# XMini.net
KiCad netlist of a schematic drawn in Altium Designer
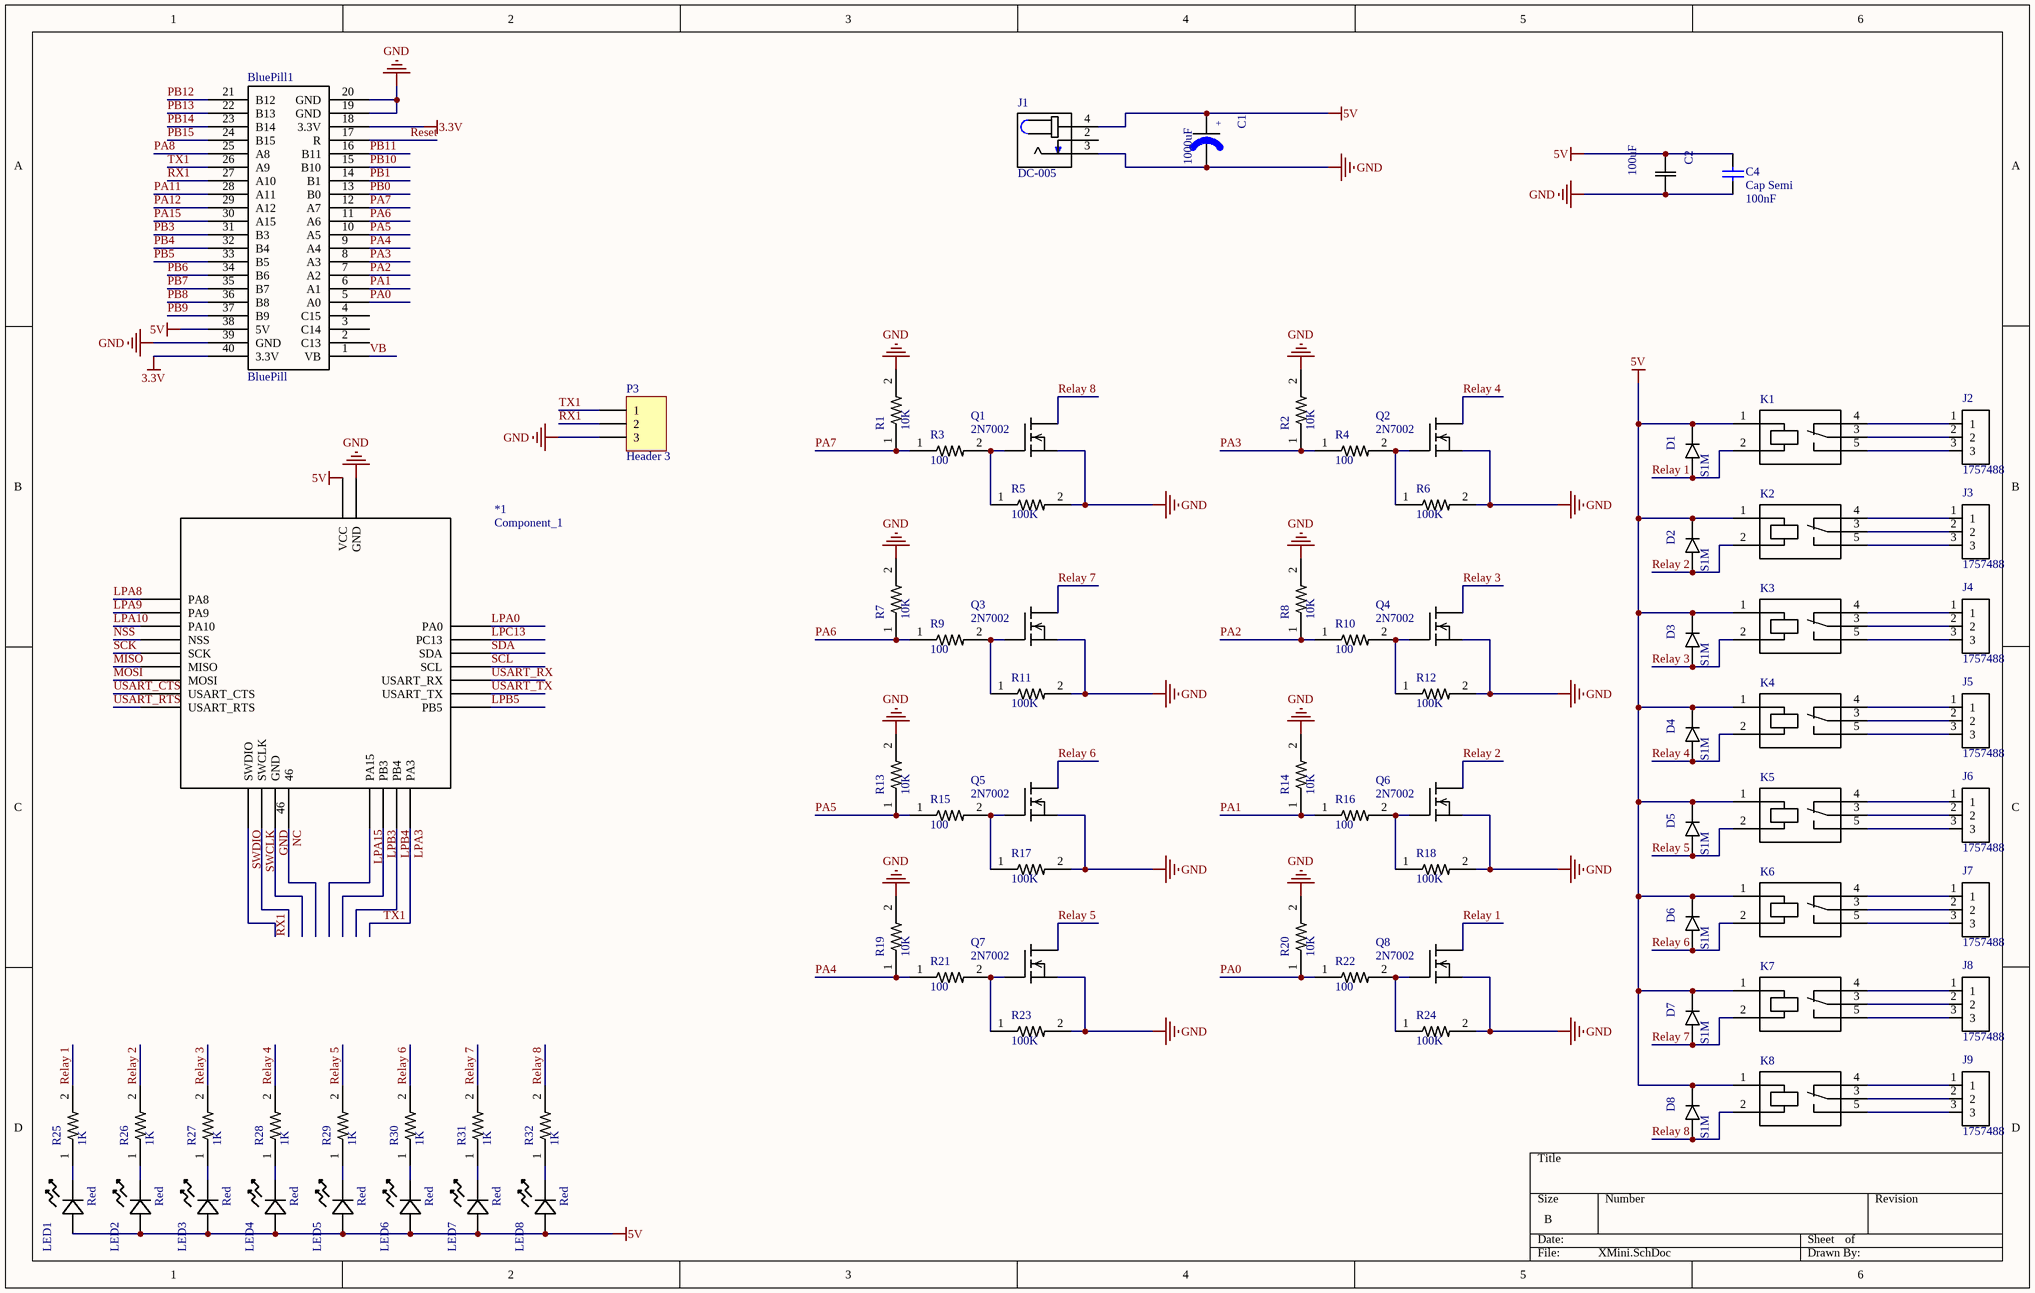
[diagram p0: XMini.SchDoc]

(export (version "E")
  (design (tool "Eeschema 10.0.6"))
  (components
    (comp (ref "*1")
      (value "Component_1")
      (footprint "Lora_Board")
      (libsource (lib "Lora Board") (part "Component_1"))
    )
    (comp (ref "BluePill1")
      (value "BluePill")
      (footprint "stm32 Blue pill")
      (description "Blue Pill Module")
      (libsource (lib "Schlib1") (part "Stm32BluePill"))
    )
    (comp (ref "C1")
      (value "1000uF")
      (footprint "*CAPAE1030X1050N")
      (fields (field (name "MF") "Cornell Dubilier") (field (name "MP") "HZA107M050G24T-F"))
      (libsource (lib "HZA107M050G24T-F") (part "HZA107M050G24T-F"))
    )
    (comp (ref "C2")
      (value "100uF")
      (footprint "*CAPCP7343X430N")
      (description "Capacitor tantalum TAJ 2717 330uF 6.3V")
      (fields (field (name "MF") "AVX") (field (name "MP") "TAJE337K006R"))
      (libsource (lib "TAJE337K006R") (part "TAJE337K006R"))
    )
    (comp (ref "C4")
      (value "Cap Semi")
      (footprint "C1206")
      (description "Capacitor (Semiconductor SIM Model)")
      (fields (field (name "ALTIUM_VALUE") "100nF") (field (name "PUBLISHER") "Altium Limited"))
      (libsource (lib "Miscellaneous Devices") (part "Cap Semi"))
    )
    (comp (ref "D1")
      (value "S1M")
      (footprint "SMD Diode*DIOM5227X270NSMD DiodeS1MSMD DiodePrimarySMD Diode")
      (description "S1 Series 1000 V 1 A 1 uA Surface Mount General Purpose Rectifier - DO-214AC")
      (fields (field (name "MF") "ON Semiconductor"))
      (libsource (lib "S1M") (part "S1M"))
    )
    (comp (ref "D2")
      (value "S1M")
      (footprint "SMD Diode*DIOM5227X270NSMD DiodeS1MSMD DiodePrimarySMD Diode")
      (description "S1 Series 1000 V 1 A 1 uA Surface Mount General Purpose Rectifier - DO-214AC")
      (fields (field (name "MF") "ON Semiconductor"))
      (libsource (lib "S1M") (part "S1M"))
    )
    (comp (ref "D3")
      (value "S1M")
      (footprint "SMD Diode*DIOM5227X270NSMD DiodeS1MSMD DiodePrimarySMD Diode")
      (description "S1 Series 1000 V 1 A 1 uA Surface Mount General Purpose Rectifier - DO-214AC")
      (fields (field (name "MF") "ON Semiconductor"))
      (libsource (lib "S1M") (part "S1M"))
    )
    (comp (ref "D4")
      (value "S1M")
      (footprint "SMD Diode*DIOM5227X270NSMD DiodeS1MSMD DiodePrimarySMD Diode")
      (description "S1 Series 1000 V 1 A 1 uA Surface Mount General Purpose Rectifier - DO-214AC")
      (fields (field (name "MF") "ON Semiconductor"))
      (libsource (lib "S1M") (part "S1M"))
    )
    (comp (ref "D5")
      (value "S1M")
      (footprint "SMD Diode*DIOM5227X270NSMD DiodeS1MSMD DiodePrimarySMD Diode")
      (description "S1 Series 1000 V 1 A 1 uA Surface Mount General Purpose Rectifier - DO-214AC")
      (fields (field (name "MF") "ON Semiconductor"))
      (libsource (lib "S1M") (part "S1M"))
    )
    (comp (ref "D6")
      (value "S1M")
      (footprint "SMD Diode*DIOM5227X270NSMD DiodeS1MSMD DiodePrimarySMD Diode")
      (description "S1 Series 1000 V 1 A 1 uA Surface Mount General Purpose Rectifier - DO-214AC")
      (fields (field (name "MF") "ON Semiconductor"))
      (libsource (lib "S1M") (part "S1M"))
    )
    (comp (ref "D7")
      (value "S1M")
      (footprint "SMD Diode*DIOM5227X270NSMD DiodeS1MSMD DiodePrimarySMD Diode")
      (description "S1 Series 1000 V 1 A 1 uA Surface Mount General Purpose Rectifier - DO-214AC")
      (fields (field (name "MF") "ON Semiconductor"))
      (libsource (lib "S1M") (part "S1M"))
    )
    (comp (ref "D8")
      (value "S1M")
      (footprint "SMD Diode*DIOM5227X270NSMD DiodeS1MSMD DiodePrimarySMD Diode")
      (description "S1 Series 1000 V 1 A 1 uA Surface Mount General Purpose Rectifier - DO-214AC")
      (fields (field (name "MF") "ON Semiconductor"))
      (libsource (lib "S1M") (part "S1M"))
    )
    (comp (ref "J1")
      (value "DC-005")
      (footprint "*NINIGI_DC-005")
      (fields (field (name "MF") "Littelfuse Inc."))
      (libsource (lib "DC-005") (part "DC-005"))
    )
    (comp (ref "J2")
      (value "1757488")
      (footprint "*PHOENIX_1757488")
      (description "Conn; TermBlk; PCB; Header; SnglLvl; 90DegAngl; Sldr; 3Pole; 5mmPitch; COMBICON")
      (fields (field (name "MF") "Phoenix Contact"))
      (libsource (lib "1757488") (part "1757488"))
    )
    (comp (ref "J3")
      (value "1757488")
      (footprint "*PHOENIX_1757488")
      (description "Conn; TermBlk; PCB; Header; SnglLvl; 90DegAngl; Sldr; 3Pole; 5mmPitch; COMBICON")
      (fields (field (name "MF") "Phoenix Contact"))
      (libsource (lib "1757488") (part "1757488"))
    )
    (comp (ref "J4")
      (value "1757488")
      (footprint "*PHOENIX_1757488")
      (description "Conn; TermBlk; PCB; Header; SnglLvl; 90DegAngl; Sldr; 3Pole; 5mmPitch; COMBICON")
      (fields (field (name "MF") "Phoenix Contact"))
      (libsource (lib "1757488") (part "1757488"))
    )
    (comp (ref "J5")
      (value "1757488")
      (footprint "*PHOENIX_1757488")
      (description "Conn; TermBlk; PCB; Header; SnglLvl; 90DegAngl; Sldr; 3Pole; 5mmPitch; COMBICON")
      (fields (field (name "MF") "Phoenix Contact"))
      (libsource (lib "1757488") (part "1757488"))
    )
    (comp (ref "J6")
      (value "1757488")
      (footprint "*PHOENIX_1757488")
      (description "Conn; TermBlk; PCB; Header; SnglLvl; 90DegAngl; Sldr; 3Pole; 5mmPitch; COMBICON")
      (fields (field (name "MF") "Phoenix Contact"))
      (libsource (lib "1757488") (part "1757488"))
    )
    (comp (ref "J7")
      (value "1757488")
      (footprint "*PHOENIX_1757488")
      (description "Conn; TermBlk; PCB; Header; SnglLvl; 90DegAngl; Sldr; 3Pole; 5mmPitch; COMBICON")
      (fields (field (name "MF") "Phoenix Contact"))
      (libsource (lib "1757488") (part "1757488"))
    )
    (comp (ref "J8")
      (value "1757488")
      (footprint "*PHOENIX_1757488")
      (description "Conn; TermBlk; PCB; Header; SnglLvl; 90DegAngl; Sldr; 3Pole; 5mmPitch; COMBICON")
      (fields (field (name "MF") "Phoenix Contact"))
      (libsource (lib "1757488") (part "1757488"))
    )
    (comp (ref "J9")
      (value "1757488")
      (footprint "*PHOENIX_1757488")
      (description "Conn; TermBlk; PCB; Header; SnglLvl; 90DegAngl; Sldr; 3Pole; 5mmPitch; COMBICON")
      (fields (field (name "MF") "Phoenix Contact"))
      (libsource (lib "1757488") (part "1757488"))
    )
    (comp (ref "K1")
      (value "1-1721150-0")
      (footprint "*TE_ORWH-SH-105D1F,000")
      (description "General Purpose Relay, ORWH Series, Power, Non Latching, SPDT, 5 VDC, 10 A")
      (fields (field (name "MF") "TE Connectivity") (field (name "MP") "ORWH-SH-105D1F,000"))
      (libsource (lib "ORWH-SH-105D1F_000") (part "ORWH-SH-105D1F,000"))
    )
    (comp (ref "K2")
      (value "1-1721150-0")
      (footprint "*TE_ORWH-SH-105D1F,000")
      (description "General Purpose Relay, ORWH Series, Power, Non Latching, SPDT, 5 VDC, 10 A")
      (fields (field (name "MF") "TE Connectivity") (field (name "MP") "ORWH-SH-105D1F,000"))
      (libsource (lib "ORWH-SH-105D1F_000") (part "ORWH-SH-105D1F,000"))
    )
    (comp (ref "K3")
      (value "1-1721150-0")
      (footprint "*TE_ORWH-SH-105D1F,000")
      (description "General Purpose Relay, ORWH Series, Power, Non Latching, SPDT, 5 VDC, 10 A")
      (fields (field (name "MF") "TE Connectivity") (field (name "MP") "ORWH-SH-105D1F,000"))
      (libsource (lib "ORWH-SH-105D1F_000") (part "ORWH-SH-105D1F,000"))
    )
    (comp (ref "K4")
      (value "1-1721150-0")
      (footprint "*TE_ORWH-SH-105D1F,000")
      (description "General Purpose Relay, ORWH Series, Power, Non Latching, SPDT, 5 VDC, 10 A")
      (fields (field (name "MF") "TE Connectivity") (field (name "MP") "ORWH-SH-105D1F,000"))
      (libsource (lib "ORWH-SH-105D1F_000") (part "ORWH-SH-105D1F,000"))
    )
    (comp (ref "K5")
      (value "1-1721150-0")
      (footprint "*TE_ORWH-SH-105D1F,000")
      (description "General Purpose Relay, ORWH Series, Power, Non Latching, SPDT, 5 VDC, 10 A")
      (fields (field (name "MF") "TE Connectivity") (field (name "MP") "ORWH-SH-105D1F,000"))
      (libsource (lib "ORWH-SH-105D1F_000") (part "ORWH-SH-105D1F,000"))
    )
    (comp (ref "K6")
      (value "1-1721150-0")
      (footprint "*TE_ORWH-SH-105D1F,000")
      (description "General Purpose Relay, ORWH Series, Power, Non Latching, SPDT, 5 VDC, 10 A")
      (fields (field (name "MF") "TE Connectivity") (field (name "MP") "ORWH-SH-105D1F,000"))
      (libsource (lib "ORWH-SH-105D1F_000") (part "ORWH-SH-105D1F,000"))
    )
    (comp (ref "K7")
      (value "1-1721150-0")
      (footprint "*TE_ORWH-SH-105D1F,000")
      (description "General Purpose Relay, ORWH Series, Power, Non Latching, SPDT, 5 VDC, 10 A")
      (fields (field (name "MF") "TE Connectivity") (field (name "MP") "ORWH-SH-105D1F,000"))
      (libsource (lib "ORWH-SH-105D1F_000") (part "ORWH-SH-105D1F,000"))
    )
    (comp (ref "K8")
      (value "1-1721150-0")
      (footprint "*TE_ORWH-SH-105D1F,000")
      (description "General Purpose Relay, ORWH Series, Power, Non Latching, SPDT, 5 VDC, 10 A")
      (fields (field (name "MF") "TE Connectivity") (field (name "MP") "ORWH-SH-105D1F,000"))
      (libsource (lib "ORWH-SH-105D1F_000") (part "ORWH-SH-105D1F,000"))
    )
    (comp (ref "LED1")
      (value "Red")
      (footprint "*LED_597-3111-407F")
      (description "LED RED CLEAR 1206 SMD")
      (fields (field (name "MF") "Dialight") (field (name "MP") "5973111407F"))
      (libsource (lib "597-3111-407F") (part "597-3111-407F"))
    )
    (comp (ref "LED2")
      (value "Red")
      (footprint "*LED_597-3111-407F")
      (description "LED RED CLEAR 1206 SMD")
      (fields (field (name "MF") "Dialight") (field (name "MP") "5973111407F"))
      (libsource (lib "597-3111-407F") (part "597-3111-407F"))
    )
    (comp (ref "LED3")
      (value "Red")
      (footprint "*LED_597-3111-407F")
      (description "LED RED CLEAR 1206 SMD")
      (fields (field (name "MF") "Dialight") (field (name "MP") "5973111407F"))
      (libsource (lib "597-3111-407F") (part "597-3111-407F"))
    )
    (comp (ref "LED4")
      (value "Red")
      (footprint "*LED_597-3111-407F")
      (description "LED RED CLEAR 1206 SMD")
      (fields (field (name "MF") "Dialight") (field (name "MP") "5973111407F"))
      (libsource (lib "597-3111-407F") (part "597-3111-407F"))
    )
    (comp (ref "LED5")
      (value "Red")
      (footprint "*LED_597-3111-407F")
      (description "LED RED CLEAR 1206 SMD")
      (fields (field (name "MF") "Dialight") (field (name "MP") "5973111407F"))
      (libsource (lib "597-3111-407F") (part "597-3111-407F"))
    )
    (comp (ref "LED6")
      (value "Red")
      (footprint "*LED_597-3111-407F")
      (description "LED RED CLEAR 1206 SMD")
      (fields (field (name "MF") "Dialight") (field (name "MP") "5973111407F"))
      (libsource (lib "597-3111-407F") (part "597-3111-407F"))
    )
    (comp (ref "LED7")
      (value "Red")
      (footprint "*LED_597-3111-407F")
      (description "LED RED CLEAR 1206 SMD")
      (fields (field (name "MF") "Dialight") (field (name "MP") "5973111407F"))
      (libsource (lib "597-3111-407F") (part "597-3111-407F"))
    )
    (comp (ref "LED8")
      (value "Red")
      (footprint "*LED_597-3111-407F")
      (description "LED RED CLEAR 1206 SMD")
      (fields (field (name "MF") "Dialight") (field (name "MP") "5973111407F"))
      (libsource (lib "597-3111-407F") (part "597-3111-407F"))
    )
    (comp (ref "P3")
      (value "Header 3")
      (footprint "HDR1X3")
      (description "Header, 3-Pin")
      (fields (field (name "PUBLISHER") "Altium Limited"))
      (libsource (lib "Miscellaneous Connectors") (part "Header 3"))
    )
    (comp (ref "Q1")
      (value "2N7002")
      (footprint "*SOT23")
      (description "Transistor NPN Mos 2N7002 SILICONIX miliampere=100 V=60 SOt23")
      (fields (field (name "MF") "STMicroelectronics"))
      (libsource (lib "2N7002") (part "2N7002"))
    )
    (comp (ref "Q2")
      (value "2N7002")
      (footprint "*SOT23")
      (description "Transistor NPN Mos 2N7002 SILICONIX miliampere=100 V=60 SOt23")
      (fields (field (name "MF") "STMicroelectronics"))
      (libsource (lib "2N7002") (part "2N7002"))
    )
    (comp (ref "Q3")
      (value "2N7002")
      (footprint "*SOT23")
      (description "Transistor NPN Mos 2N7002 SILICONIX miliampere=100 V=60 SOt23")
      (fields (field (name "MF") "STMicroelectronics"))
      (libsource (lib "2N7002") (part "2N7002"))
    )
    (comp (ref "Q4")
      (value "2N7002")
      (footprint "*SOT23")
      (description "Transistor NPN Mos 2N7002 SILICONIX miliampere=100 V=60 SOt23")
      (fields (field (name "MF") "STMicroelectronics"))
      (libsource (lib "2N7002") (part "2N7002"))
    )
    (comp (ref "Q5")
      (value "2N7002")
      (footprint "*SOT23")
      (description "Transistor NPN Mos 2N7002 SILICONIX miliampere=100 V=60 SOt23")
      (fields (field (name "MF") "STMicroelectronics"))
      (libsource (lib "2N7002") (part "2N7002"))
    )
    (comp (ref "Q6")
      (value "2N7002")
      (footprint "*SOT23")
      (description "Transistor NPN Mos 2N7002 SILICONIX miliampere=100 V=60 SOt23")
      (fields (field (name "MF") "STMicroelectronics"))
      (libsource (lib "2N7002") (part "2N7002"))
    )
    (comp (ref "Q7")
      (value "2N7002")
      (footprint "*SOT23")
      (description "Transistor NPN Mos 2N7002 SILICONIX miliampere=100 V=60 SOt23")
      (fields (field (name "MF") "STMicroelectronics"))
      (libsource (lib "2N7002") (part "2N7002"))
    )
    (comp (ref "Q8")
      (value "2N7002")
      (footprint "*SOT23")
      (description "Transistor NPN Mos 2N7002 SILICONIX miliampere=100 V=60 SOt23")
      (fields (field (name "MF") "STMicroelectronics"))
      (libsource (lib "2N7002") (part "2N7002"))
    )
    (comp (ref "R1")
      (value "10K")
      (footprint "*RESC3116X65N")
      (description "Res Smd 120k Ohm 0.5% 1/8w 1206")
      (fields (field (name "MF") "Yageo") (field (name "MP") "RT1206DRE07120KL"))
      (libsource (lib "RT1206DRE07120KL") (part "RT1206DRE07120KL"))
    )
    (comp (ref "R2")
      (value "10K")
      (footprint "*RESC3116X65N")
      (description "Res Smd 120k Ohm 0.5% 1/8w 1206")
      (fields (field (name "MF") "Yageo") (field (name "MP") "RT1206DRE07120KL"))
      (libsource (lib "RT1206DRE07120KL") (part "RT1206DRE07120KL"))
    )
    (comp (ref "R3")
      (value "100")
      (footprint "*RESC3116X65N")
      (description "Res Smd 120k Ohm 0.5% 1/8w 1206")
      (fields (field (name "MF") "Yageo") (field (name "MP") "RT1206DRE07120KL"))
      (libsource (lib "RT1206DRE07120KL") (part "RT1206DRE07120KL"))
    )
    (comp (ref "R4")
      (value "100")
      (footprint "*RESC3116X65N")
      (description "Res Smd 120k Ohm 0.5% 1/8w 1206")
      (fields (field (name "MF") "Yageo") (field (name "MP") "RT1206DRE07120KL"))
      (libsource (lib "RT1206DRE07120KL") (part "RT1206DRE07120KL"))
    )
    (comp (ref "R5")
      (value "100K")
      (footprint "*RESC3116X65N")
      (description "Res Smd 120k Ohm 0.5% 1/8w 1206")
      (fields (field (name "MF") "Yageo") (field (name "MP") "RT1206DRE07120KL"))
      (libsource (lib "RT1206DRE07120KL") (part "RT1206DRE07120KL"))
    )
    (comp (ref "R6")
      (value "100K")
      (footprint "*RESC3116X65N")
      (description "Res Smd 120k Ohm 0.5% 1/8w 1206")
      (fields (field (name "MF") "Yageo") (field (name "MP") "RT1206DRE07120KL"))
      (libsource (lib "RT1206DRE07120KL") (part "RT1206DRE07120KL"))
    )
    (comp (ref "R7")
      (value "10K")
      (footprint "*RESC3116X65N")
      (description "Res Smd 120k Ohm 0.5% 1/8w 1206")
      (fields (field (name "MF") "Yageo") (field (name "MP") "RT1206DRE07120KL"))
      (libsource (lib "RT1206DRE07120KL") (part "RT1206DRE07120KL"))
    )
    (comp (ref "R8")
      (value "10K")
      (footprint "*RESC3116X65N")
      (description "Res Smd 120k Ohm 0.5% 1/8w 1206")
      (fields (field (name "MF") "Yageo") (field (name "MP") "RT1206DRE07120KL"))
      (libsource (lib "RT1206DRE07120KL") (part "RT1206DRE07120KL"))
    )
    (comp (ref "R9")
      (value "100")
      (footprint "*RESC3116X65N")
      (description "Res Smd 120k Ohm 0.5% 1/8w 1206")
      (fields (field (name "MF") "Yageo") (field (name "MP") "RT1206DRE07120KL"))
      (libsource (lib "RT1206DRE07120KL") (part "RT1206DRE07120KL"))
    )
    (comp (ref "R10")
      (value "100")
      (footprint "*RESC3116X65N")
      (description "Res Smd 120k Ohm 0.5% 1/8w 1206")
      (fields (field (name "MF") "Yageo") (field (name "MP") "RT1206DRE07120KL"))
      (libsource (lib "RT1206DRE07120KL") (part "RT1206DRE07120KL"))
    )
    (comp (ref "R11")
      (value "100K")
      (footprint "*RESC3116X65N")
      (description "Res Smd 120k Ohm 0.5% 1/8w 1206")
      (fields (field (name "MF") "Yageo") (field (name "MP") "RT1206DRE07120KL"))
      (libsource (lib "RT1206DRE07120KL") (part "RT1206DRE07120KL"))
    )
    (comp (ref "R12")
      (value "100K")
      (footprint "*RESC3116X65N")
      (description "Res Smd 120k Ohm 0.5% 1/8w 1206")
      (fields (field (name "MF") "Yageo") (field (name "MP") "RT1206DRE07120KL"))
      (libsource (lib "RT1206DRE07120KL") (part "RT1206DRE07120KL"))
    )
    (comp (ref "R13")
      (value "10K")
      (footprint "*RESC3116X65N")
      (description "Res Smd 120k Ohm 0.5% 1/8w 1206")
      (fields (field (name "MF") "Yageo") (field (name "MP") "RT1206DRE07120KL"))
      (libsource (lib "RT1206DRE07120KL") (part "RT1206DRE07120KL"))
    )
    (comp (ref "R14")
      (value "10K")
      (footprint "*RESC3116X65N")
      (description "Res Smd 120k Ohm 0.5% 1/8w 1206")
      (fields (field (name "MF") "Yageo") (field (name "MP") "RT1206DRE07120KL"))
      (libsource (lib "RT1206DRE07120KL") (part "RT1206DRE07120KL"))
    )
    (comp (ref "R15")
      (value "100")
      (footprint "*RESC3116X65N")
      (description "Res Smd 120k Ohm 0.5% 1/8w 1206")
      (fields (field (name "MF") "Yageo") (field (name "MP") "RT1206DRE07120KL"))
      (libsource (lib "RT1206DRE07120KL") (part "RT1206DRE07120KL"))
    )
    (comp (ref "R16")
      (value "100")
      (footprint "*RESC3116X65N")
      (description "Res Smd 120k Ohm 0.5% 1/8w 1206")
      (fields (field (name "MF") "Yageo") (field (name "MP") "RT1206DRE07120KL"))
      (libsource (lib "RT1206DRE07120KL") (part "RT1206DRE07120KL"))
    )
    (comp (ref "R17")
      (value "100K")
      (footprint "*RESC3116X65N")
      (description "Res Smd 120k Ohm 0.5% 1/8w 1206")
      (fields (field (name "MF") "Yageo") (field (name "MP") "RT1206DRE07120KL"))
      (libsource (lib "RT1206DRE07120KL") (part "RT1206DRE07120KL"))
    )
    (comp (ref "R18")
      (value "100K")
      (footprint "*RESC3116X65N")
      (description "Res Smd 120k Ohm 0.5% 1/8w 1206")
      (fields (field (name "MF") "Yageo") (field (name "MP") "RT1206DRE07120KL"))
      (libsource (lib "RT1206DRE07120KL") (part "RT1206DRE07120KL"))
    )
    (comp (ref "R19")
      (value "10K")
      (footprint "*RESC3116X65N")
      (description "Res Smd 120k Ohm 0.5% 1/8w 1206")
      (fields (field (name "MF") "Yageo") (field (name "MP") "RT1206DRE07120KL"))
      (libsource (lib "RT1206DRE07120KL") (part "RT1206DRE07120KL"))
    )
    (comp (ref "R20")
      (value "10K")
      (footprint "*RESC3116X65N")
      (description "Res Smd 120k Ohm 0.5% 1/8w 1206")
      (fields (field (name "MF") "Yageo") (field (name "MP") "RT1206DRE07120KL"))
      (libsource (lib "RT1206DRE07120KL") (part "RT1206DRE07120KL"))
    )
    (comp (ref "R21")
      (value "100")
      (footprint "*RESC3116X65N")
      (description "Res Smd 120k Ohm 0.5% 1/8w 1206")
      (fields (field (name "MF") "Yageo") (field (name "MP") "RT1206DRE07120KL"))
      (libsource (lib "RT1206DRE07120KL") (part "RT1206DRE07120KL"))
    )
    (comp (ref "R22")
      (value "100")
      (footprint "*RESC3116X65N")
      (description "Res Smd 120k Ohm 0.5% 1/8w 1206")
      (fields (field (name "MF") "Yageo") (field (name "MP") "RT1206DRE07120KL"))
      (libsource (lib "RT1206DRE07120KL") (part "RT1206DRE07120KL"))
    )
    (comp (ref "R23")
      (value "100K")
      (footprint "*RESC3116X65N")
      (description "Res Smd 120k Ohm 0.5% 1/8w 1206")
      (fields (field (name "MF") "Yageo") (field (name "MP") "RT1206DRE07120KL"))
      (libsource (lib "RT1206DRE07120KL") (part "RT1206DRE07120KL"))
    )
    (comp (ref "R24")
      (value "100K")
      (footprint "*RESC3116X65N")
      (description "Res Smd 120k Ohm 0.5% 1/8w 1206")
      (fields (field (name "MF") "Yageo") (field (name "MP") "RT1206DRE07120KL"))
      (libsource (lib "RT1206DRE07120KL") (part "RT1206DRE07120KL"))
    )
    (comp (ref "R25")
      (value "1K")
      (footprint "*RESC3116X65N")
      (description "Res Smd 120k Ohm 0.5% 1/8w 1206")
      (fields (field (name "MF") "Yageo") (field (name "MP") "RT1206DRE07120KL"))
      (libsource (lib "RT1206DRE07120KL") (part "RT1206DRE07120KL"))
    )
    (comp (ref "R26")
      (value "1K")
      (footprint "*RESC3116X65N")
      (description "Res Smd 120k Ohm 0.5% 1/8w 1206")
      (fields (field (name "MF") "Yageo") (field (name "MP") "RT1206DRE07120KL"))
      (libsource (lib "RT1206DRE07120KL") (part "RT1206DRE07120KL"))
    )
    (comp (ref "R27")
      (value "1K")
      (footprint "*RESC3116X65N")
      (description "Res Smd 120k Ohm 0.5% 1/8w 1206")
      (fields (field (name "MF") "Yageo") (field (name "MP") "RT1206DRE07120KL"))
      (libsource (lib "RT1206DRE07120KL") (part "RT1206DRE07120KL"))
    )
    (comp (ref "R28")
      (value "1K")
      (footprint "*RESC3116X65N")
      (description "Res Smd 120k Ohm 0.5% 1/8w 1206")
      (fields (field (name "MF") "Yageo") (field (name "MP") "RT1206DRE07120KL"))
      (libsource (lib "RT1206DRE07120KL") (part "RT1206DRE07120KL"))
    )
    (comp (ref "R29")
      (value "1K")
      (footprint "*RESC3116X65N")
      (description "Res Smd 120k Ohm 0.5% 1/8w 1206")
      (fields (field (name "MF") "Yageo") (field (name "MP") "RT1206DRE07120KL"))
      (libsource (lib "RT1206DRE07120KL") (part "RT1206DRE07120KL"))
    )
    (comp (ref "R30")
      (value "1K")
      (footprint "*RESC3116X65N")
      (description "Res Smd 120k Ohm 0.5% 1/8w 1206")
      (fields (field (name "MF") "Yageo") (field (name "MP") "RT1206DRE07120KL"))
      (libsource (lib "RT1206DRE07120KL") (part "RT1206DRE07120KL"))
    )
    (comp (ref "R31")
      (value "1K")
      (footprint "*RESC3116X65N")
      (description "Res Smd 120k Ohm 0.5% 1/8w 1206")
      (fields (field (name "MF") "Yageo") (field (name "MP") "RT1206DRE07120KL"))
      (libsource (lib "RT1206DRE07120KL") (part "RT1206DRE07120KL"))
    )
    (comp (ref "R32")
      (value "1K")
      (footprint "*RESC3116X65N")
      (description "Res Smd 120k Ohm 0.5% 1/8w 1206")
      (fields (field (name "MF") "Yageo") (field (name "MP") "RT1206DRE07120KL"))
      (libsource (lib "RT1206DRE07120KL") (part "RT1206DRE07120KL"))
    )
  )
  (nets
    (net (code "1") (name "/LPA0") (class "Default")
      (node (ref "*1") (pin "PA0") (pinfunction "PA0_PA0") (pintype "power_in"))
    )
    (net (code "2") (name "/LPA3") (class "Default")
      (node (ref "*1") (pin "PA3") (pinfunction "PA3_PA3") (pintype "power_in"))
      (node (ref "BluePill1") (pin "26") (pinfunction "A9_26") (pintype "power_in"))
      (node (ref "P3") (pin "1") (pinfunction "1_1") (pintype "passive"))
    )
    (net (code "3") (name "/LPA8") (class "Default")
      (node (ref "*1") (pin "PA8") (pinfunction "PA8_PA8") (pintype "power_in"))
    )
    (net (code "4") (name "/LPA9") (class "Default")
      (node (ref "*1") (pin "PA9") (pinfunction "PA9_PA9") (pintype "power_in"))
    )
    (net (code "5") (name "/LPA10") (class "Default")
      (node (ref "*1") (pin "PA10") (pinfunction "PA10_PA10") (pintype "power_in"))
    )
    (net (code "6") (name "/LPA15") (class "Default")
      (node (ref "*1") (pin "PA15") (pinfunction "PA15_PA15") (pintype "power_in"))
    )
    (net (code "7") (name "/LPB3") (class "Default")
      (node (ref "*1") (pin "PB3") (pinfunction "PB3_PB3") (pintype "power_in"))
    )
    (net (code "8") (name "/LPB4") (class "Default")
      (node (ref "*1") (pin "PB4") (pinfunction "PB4_PB4") (pintype "power_in"))
    )
    (net (code "9") (name "/LPB5") (class "Default")
      (node (ref "*1") (pin "PB5") (pinfunction "PB5_PB5") (pintype "power_in"))
    )
    (net (code "10") (name "/LPC13") (class "Default")
      (node (ref "*1") (pin "PC13") (pinfunction "PC13_PC13") (pintype "power_in"))
    )
    (net (code "11") (name "/MISO") (class "Default")
      (node (ref "*1") (pin "MISO") (pinfunction "MISO_MISO") (pintype "power_in"))
    )
    (net (code "12") (name "/MOSI") (class "Default")
      (node (ref "*1") (pin "MOSI") (pinfunction "MOSI_MOSI") (pintype "power_in"))
    )
    (net (code "13") (name "/NC") (class "Default")
      (node (ref "*1") (pin "46") (pinfunction "46_46") (pintype "power_in"))
    )
    (net (code "14") (name "/NSS") (class "Default")
      (node (ref "*1") (pin "NSS") (pinfunction "NSS_NSS") (pintype "power_in"))
    )
    (net (code "15") (name "/PA0") (class "Default")
      (node (ref "BluePill1") (pin "5") (pinfunction "A0_5") (pintype "power_in"))
      (node (ref "R20") (pin "1") (pinfunction "1_1") (pintype "passive"))
      (node (ref "R22") (pin "1") (pinfunction "1_1") (pintype "passive"))
    )
    (net (code "16") (name "/PA1") (class "Default")
      (node (ref "BluePill1") (pin "6") (pinfunction "A1_6") (pintype "power_in"))
      (node (ref "R14") (pin "1") (pinfunction "1_1") (pintype "passive"))
      (node (ref "R16") (pin "1") (pinfunction "1_1") (pintype "passive"))
    )
    (net (code "17") (name "/PA2") (class "Default")
      (node (ref "BluePill1") (pin "7") (pinfunction "A2_7") (pintype "power_in"))
      (node (ref "R10") (pin "1") (pinfunction "1_1") (pintype "passive"))
      (node (ref "R8") (pin "1") (pinfunction "1_1") (pintype "passive"))
    )
    (net (code "18") (name "/PA3") (class "Default")
      (node (ref "BluePill1") (pin "8") (pinfunction "A3_8") (pintype "power_in"))
      (node (ref "R2") (pin "1") (pinfunction "1_1") (pintype "passive"))
      (node (ref "R4") (pin "1") (pinfunction "1_1") (pintype "passive"))
    )
    (net (code "19") (name "/PA4") (class "Default")
      (node (ref "BluePill1") (pin "9") (pinfunction "A4_9") (pintype "power_in"))
      (node (ref "R19") (pin "1") (pinfunction "1_1") (pintype "passive"))
      (node (ref "R21") (pin "1") (pinfunction "1_1") (pintype "passive"))
    )
    (net (code "20") (name "/PA5") (class "Default")
      (node (ref "BluePill1") (pin "10") (pinfunction "A5_10") (pintype "power_in"))
      (node (ref "R13") (pin "1") (pinfunction "1_1") (pintype "passive"))
      (node (ref "R15") (pin "1") (pinfunction "1_1") (pintype "passive"))
    )
    (net (code "21") (name "/PA6") (class "Default")
      (node (ref "BluePill1") (pin "11") (pinfunction "A6_11") (pintype "power_in"))
      (node (ref "R7") (pin "1") (pinfunction "1_1") (pintype "passive"))
      (node (ref "R9") (pin "1") (pinfunction "1_1") (pintype "passive"))
    )
    (net (code "22") (name "/PA7") (class "Default")
      (node (ref "BluePill1") (pin "12") (pinfunction "A7_12") (pintype "power_in"))
      (node (ref "R1") (pin "1") (pinfunction "1_1") (pintype "passive"))
      (node (ref "R3") (pin "1") (pinfunction "1_1") (pintype "passive"))
    )
    (net (code "23") (name "/PA8") (class "Default")
      (node (ref "BluePill1") (pin "25") (pinfunction "A8_25") (pintype "power_in"))
    )
    (net (code "24") (name "/PA11") (class "Default")
      (node (ref "BluePill1") (pin "28") (pinfunction "A11_28") (pintype "power_in"))
    )
    (net (code "25") (name "/PA12") (class "Default")
      (node (ref "BluePill1") (pin "29") (pinfunction "A12_29") (pintype "power_in"))
    )
    (net (code "26") (name "/PA15") (class "Default")
      (node (ref "BluePill1") (pin "30") (pinfunction "A15_30") (pintype "power_in"))
    )
    (net (code "27") (name "/PB0") (class "Default")
      (node (ref "BluePill1") (pin "13") (pinfunction "B0_13") (pintype "power_in"))
    )
    (net (code "28") (name "/PB1") (class "Default")
      (node (ref "BluePill1") (pin "14") (pinfunction "B1_14") (pintype "power_in"))
    )
    (net (code "29") (name "/PB3") (class "Default")
      (node (ref "BluePill1") (pin "31") (pinfunction "B3_31") (pintype "power_in"))
    )
    (net (code "30") (name "/PB4") (class "Default")
      (node (ref "BluePill1") (pin "32") (pinfunction "B4_32") (pintype "power_in"))
    )
    (net (code "31") (name "/PB5") (class "Default")
      (node (ref "BluePill1") (pin "33") (pinfunction "B5_33") (pintype "power_in"))
    )
    (net (code "32") (name "/PB6") (class "Default")
      (node (ref "BluePill1") (pin "34") (pinfunction "B6_34") (pintype "power_in"))
    )
    (net (code "33") (name "/PB7") (class "Default")
      (node (ref "BluePill1") (pin "35") (pinfunction "B7_35") (pintype "power_in"))
    )
    (net (code "34") (name "/PB8") (class "Default")
      (node (ref "BluePill1") (pin "36") (pinfunction "B8_36") (pintype "power_in"))
    )
    (net (code "35") (name "/PB9") (class "Default")
      (node (ref "BluePill1") (pin "37") (pinfunction "B9_37") (pintype "power_in"))
    )
    (net (code "36") (name "/PB10") (class "Default")
      (node (ref "BluePill1") (pin "15") (pinfunction "B10_15") (pintype "power_in"))
    )
    (net (code "37") (name "/PB11") (class "Default")
      (node (ref "BluePill1") (pin "16") (pinfunction "B11_16") (pintype "power_in"))
    )
    (net (code "38") (name "/PB12") (class "Default")
      (node (ref "BluePill1") (pin "21") (pinfunction "B12_21") (pintype "power_in"))
    )
    (net (code "39") (name "/PB13") (class "Default")
      (node (ref "BluePill1") (pin "22") (pinfunction "B13_22") (pintype "power_in"))
    )
    (net (code "40") (name "/PB14") (class "Default")
      (node (ref "BluePill1") (pin "23") (pinfunction "B14_23") (pintype "power_in"))
    )
    (net (code "41") (name "/PB15") (class "Default")
      (node (ref "BluePill1") (pin "24") (pinfunction "B15_24") (pintype "power_in"))
    )
    (net (code "42") (name "/RX1") (class "Default")
      (node (ref "*1") (pin "SWCLK") (pinfunction "SWCLK_SWCLK") (pintype "power_in"))
      (node (ref "BluePill1") (pin "27") (pinfunction "A10_27") (pintype "power_in"))
      (node (ref "P3") (pin "2") (pinfunction "2_2") (pintype "passive"))
    )
    (net (code "43") (name "/Relay 1") (class "Default")
      (node (ref "D1") (pin "A") (pinfunction "A_A") (pintype "passive"))
      (node (ref "K1") (pin "2") (pinfunction "C2_2") (pintype "passive"))
      (node (ref "Q8") (pin "3") (pinfunction "D_3") (pintype "passive"))
      (node (ref "R25") (pin "2") (pinfunction "2_2") (pintype "passive"))
    )
    (net (code "44") (name "/Relay 2") (class "Default")
      (node (ref "D2") (pin "A") (pinfunction "A_A") (pintype "passive"))
      (node (ref "K2") (pin "2") (pinfunction "C2_2") (pintype "passive"))
      (node (ref "Q6") (pin "3") (pinfunction "D_3") (pintype "passive"))
      (node (ref "R26") (pin "2") (pinfunction "2_2") (pintype "passive"))
    )
    (net (code "45") (name "/Relay 3") (class "Default")
      (node (ref "D3") (pin "A") (pinfunction "A_A") (pintype "passive"))
      (node (ref "K3") (pin "2") (pinfunction "C2_2") (pintype "passive"))
      (node (ref "Q4") (pin "3") (pinfunction "D_3") (pintype "passive"))
      (node (ref "R27") (pin "2") (pinfunction "2_2") (pintype "passive"))
    )
    (net (code "46") (name "/Relay 4") (class "Default")
      (node (ref "D4") (pin "A") (pinfunction "A_A") (pintype "passive"))
      (node (ref "K4") (pin "2") (pinfunction "C2_2") (pintype "passive"))
      (node (ref "Q2") (pin "3") (pinfunction "D_3") (pintype "passive"))
      (node (ref "R28") (pin "2") (pinfunction "2_2") (pintype "passive"))
    )
    (net (code "47") (name "/Relay 5") (class "Default")
      (node (ref "D5") (pin "A") (pinfunction "A_A") (pintype "passive"))
      (node (ref "K5") (pin "2") (pinfunction "C2_2") (pintype "passive"))
      (node (ref "Q7") (pin "3") (pinfunction "D_3") (pintype "passive"))
      (node (ref "R29") (pin "2") (pinfunction "2_2") (pintype "passive"))
    )
    (net (code "48") (name "/Relay 6") (class "Default")
      (node (ref "D6") (pin "A") (pinfunction "A_A") (pintype "passive"))
      (node (ref "K6") (pin "2") (pinfunction "C2_2") (pintype "passive"))
      (node (ref "Q5") (pin "3") (pinfunction "D_3") (pintype "passive"))
      (node (ref "R30") (pin "2") (pinfunction "2_2") (pintype "passive"))
    )
    (net (code "49") (name "/Relay 7") (class "Default")
      (node (ref "D7") (pin "A") (pinfunction "A_A") (pintype "passive"))
      (node (ref "K7") (pin "2") (pinfunction "C2_2") (pintype "passive"))
      (node (ref "Q3") (pin "3") (pinfunction "D_3") (pintype "passive"))
      (node (ref "R31") (pin "2") (pinfunction "2_2") (pintype "passive"))
    )
    (net (code "50") (name "/Relay 8") (class "Default")
      (node (ref "D8") (pin "A") (pinfunction "A_A") (pintype "passive"))
      (node (ref "K8") (pin "2") (pinfunction "C2_2") (pintype "passive"))
      (node (ref "Q1") (pin "3") (pinfunction "D_3") (pintype "passive"))
      (node (ref "R32") (pin "2") (pinfunction "2_2") (pintype "passive"))
    )
    (net (code "51") (name "/Reset") (class "Default")
      (node (ref "BluePill1") (pin "17") (pinfunction "R_17") (pintype "power_in"))
    )
    (net (code "52") (name "/SCK") (class "Default")
      (node (ref "*1") (pin "SCK") (pinfunction "SCK_SCK") (pintype "power_in"))
    )
    (net (code "53") (name "/SCL") (class "Default")
      (node (ref "*1") (pin "SCL") (pinfunction "SCL_SCL") (pintype "power_in"))
    )
    (net (code "54") (name "/SDA") (class "Default")
      (node (ref "*1") (pin "SDA") (pinfunction "SDA_SDA") (pintype "power_in"))
    )
    (net (code "55") (name "/SWDIO") (class "Default")
      (node (ref "*1") (pin "SWDIO") (pinfunction "SWDIO_SWDIO") (pintype "power_in"))
    )
    (net (code "56") (name "/USART_CTS") (class "Default")
      (node (ref "*1") (pin "USART_CTS") (pinfunction "USART_CTS_USART_CTS") (pintype "power_in"))
    )
    (net (code "57") (name "/USART_RTS") (class "Default")
      (node (ref "*1") (pin "USART_RTS") (pinfunction "USART_RTS_USART_RTS") (pintype "power_in"))
    )
    (net (code "58") (name "/USART_RX") (class "Default")
      (node (ref "*1") (pin "USART_RX") (pinfunction "USART_RX_USART_RX") (pintype "power_in"))
    )
    (net (code "59") (name "/USART_TX") (class "Default")
      (node (ref "*1") (pin "USART_TX") (pinfunction "USART_TX_USART_TX") (pintype "power_in"))
    )
    (net (code "60") (name "/VB") (class "Default")
      (node (ref "BluePill1") (pin "1") (pinfunction "VB_1") (pintype "power_in"))
    )
    (net (code "61") (name "3.3V") (class "Default")
      (node (ref "BluePill1") (pin "18") (pinfunction "3.3V_18") (pintype "power_in"))
      (node (ref "BluePill1") (pin "40") (pinfunction "3.3V_40") (pintype "power_in"))
    )
    (net (code "62") (name "5V") (class "Default")
      (node (ref "*1") (pin "VCC") (pinfunction "VCC_VCC") (pintype "power_in"))
      (node (ref "BluePill1") (pin "38") (pinfunction "5V_38") (pintype "power_in"))
      (node (ref "C1") (pin "1") (pinfunction "1_1") (pintype "passive"))
      (node (ref "C2") (pin "1") (pinfunction "C1_1") (pintype "passive"))
      (node (ref "C4") (pin "2") (pinfunction "2_2") (pintype "passive"))
      (node (ref "D1") (pin "C") (pinfunction "K_C") (pintype "passive"))
      (node (ref "D2") (pin "C") (pinfunction "K_C") (pintype "passive"))
      (node (ref "D3") (pin "C") (pinfunction "K_C") (pintype "passive"))
      (node (ref "D4") (pin "C") (pinfunction "K_C") (pintype "passive"))
      (node (ref "D5") (pin "C") (pinfunction "K_C") (pintype "passive"))
      (node (ref "D6") (pin "C") (pinfunction "K_C") (pintype "passive"))
      (node (ref "D7") (pin "C") (pinfunction "K_C") (pintype "passive"))
      (node (ref "D8") (pin "C") (pinfunction "K_C") (pintype "passive"))
      (node (ref "J1") (pin "4") (pinfunction "2_4") (pintype "passive"))
      (node (ref "K1") (pin "1") (pinfunction "C1_1") (pintype "passive"))
      (node (ref "K2") (pin "1") (pinfunction "C1_1") (pintype "passive"))
      (node (ref "K3") (pin "1") (pinfunction "C1_1") (pintype "passive"))
      (node (ref "K4") (pin "1") (pinfunction "C1_1") (pintype "passive"))
      (node (ref "K5") (pin "1") (pinfunction "C1_1") (pintype "passive"))
      (node (ref "K6") (pin "1") (pinfunction "C1_1") (pintype "passive"))
      (node (ref "K7") (pin "1") (pinfunction "C1_1") (pintype "passive"))
      (node (ref "K8") (pin "1") (pinfunction "C1_1") (pintype "passive"))
      (node (ref "LED1") (pin "2") (pinfunction "2_2") (pintype "passive"))
      (node (ref "LED2") (pin "2") (pinfunction "2_2") (pintype "passive"))
      (node (ref "LED3") (pin "2") (pinfunction "2_2") (pintype "passive"))
      (node (ref "LED4") (pin "2") (pinfunction "2_2") (pintype "passive"))
      (node (ref "LED5") (pin "2") (pinfunction "2_2") (pintype "passive"))
      (node (ref "LED6") (pin "2") (pinfunction "2_2") (pintype "passive"))
      (node (ref "LED7") (pin "2") (pinfunction "2_2") (pintype "passive"))
      (node (ref "LED8") (pin "2") (pinfunction "2_2") (pintype "passive"))
    )
    (net (code "63") (name "GND") (class "Default")
      (node (ref "*1") (pin "GND") (pinfunction "GND_GND") (pintype "power_in"))
      (node (ref "BluePill1") (pin "19") (pinfunction "GND_19") (pintype "power_in"))
      (node (ref "BluePill1") (pin "20") (pinfunction "GND_20") (pintype "power_in"))
      (node (ref "BluePill1") (pin "39") (pinfunction "GND_39") (pintype "power_in"))
      (node (ref "C1") (pin "2") (pinfunction "2_2") (pintype "passive"))
      (node (ref "C2") (pin "2") (pinfunction "C2_2") (pintype "passive"))
      (node (ref "C4") (pin "1") (pinfunction "1_1") (pintype "passive"))
      (node (ref "J1") (pin "3") (pinfunction "5_3") (pintype "passive"))
      (node (ref "P3") (pin "3") (pinfunction "3_3") (pintype "passive"))
      (node (ref "Q1") (pin "2") (pinfunction "S_2") (pintype "passive"))
      (node (ref "Q2") (pin "2") (pinfunction "S_2") (pintype "passive"))
      (node (ref "Q3") (pin "2") (pinfunction "S_2") (pintype "passive"))
      (node (ref "Q4") (pin "2") (pinfunction "S_2") (pintype "passive"))
      (node (ref "Q5") (pin "2") (pinfunction "S_2") (pintype "passive"))
      (node (ref "Q6") (pin "2") (pinfunction "S_2") (pintype "passive"))
      (node (ref "Q7") (pin "2") (pinfunction "S_2") (pintype "passive"))
      (node (ref "Q8") (pin "2") (pinfunction "S_2") (pintype "passive"))
      (node (ref "R1") (pin "2") (pinfunction "2_2") (pintype "passive"))
      (node (ref "R11") (pin "2") (pinfunction "2_2") (pintype "passive"))
      (node (ref "R12") (pin "2") (pinfunction "2_2") (pintype "passive"))
      (node (ref "R13") (pin "2") (pinfunction "2_2") (pintype "passive"))
      (node (ref "R14") (pin "2") (pinfunction "2_2") (pintype "passive"))
      (node (ref "R17") (pin "2") (pinfunction "2_2") (pintype "passive"))
      (node (ref "R18") (pin "2") (pinfunction "2_2") (pintype "passive"))
      (node (ref "R19") (pin "2") (pinfunction "2_2") (pintype "passive"))
      (node (ref "R2") (pin "2") (pinfunction "2_2") (pintype "passive"))
      (node (ref "R20") (pin "2") (pinfunction "2_2") (pintype "passive"))
      (node (ref "R23") (pin "2") (pinfunction "2_2") (pintype "passive"))
      (node (ref "R24") (pin "2") (pinfunction "2_2") (pintype "passive"))
      (node (ref "R5") (pin "2") (pinfunction "2_2") (pintype "passive"))
      (node (ref "R6") (pin "2") (pinfunction "2_2") (pintype "passive"))
      (node (ref "R7") (pin "2") (pinfunction "2_2") (pintype "passive"))
      (node (ref "R8") (pin "2") (pinfunction "2_2") (pintype "passive"))
    )
    (net (code "64") (name "Net-(K1-C)") (class "Default")
      (node (ref "J2") (pin "2") (pinfunction "2_2") (pintype "passive"))
      (node (ref "K1") (pin "3") (pinfunction "C_3") (pintype "passive"))
    )
    (net (code "65") (name "Net-(K1-NC)") (class "Default")
      (node (ref "J2") (pin "1") (pinfunction "1_1") (pintype "passive"))
      (node (ref "K1") (pin "4") (pinfunction "NC_4") (pintype "passive"))
    )
    (net (code "66") (name "Net-(K1-NO)") (class "Default")
      (node (ref "J2") (pin "3") (pinfunction "3_3") (pintype "passive"))
      (node (ref "K1") (pin "5") (pinfunction "NO_5") (pintype "passive"))
    )
    (net (code "67") (name "Net-(K2-C)") (class "Default")
      (node (ref "J3") (pin "2") (pinfunction "2_2") (pintype "passive"))
      (node (ref "K2") (pin "3") (pinfunction "C_3") (pintype "passive"))
    )
    (net (code "68") (name "Net-(K2-NC)") (class "Default")
      (node (ref "J3") (pin "1") (pinfunction "1_1") (pintype "passive"))
      (node (ref "K2") (pin "4") (pinfunction "NC_4") (pintype "passive"))
    )
    (net (code "69") (name "Net-(K2-NO)") (class "Default")
      (node (ref "J3") (pin "3") (pinfunction "3_3") (pintype "passive"))
      (node (ref "K2") (pin "5") (pinfunction "NO_5") (pintype "passive"))
    )
    (net (code "70") (name "Net-(K3-C)") (class "Default")
      (node (ref "J4") (pin "2") (pinfunction "2_2") (pintype "passive"))
      (node (ref "K3") (pin "3") (pinfunction "C_3") (pintype "passive"))
    )
    (net (code "71") (name "Net-(K3-NC)") (class "Default")
      (node (ref "J4") (pin "1") (pinfunction "1_1") (pintype "passive"))
      (node (ref "K3") (pin "4") (pinfunction "NC_4") (pintype "passive"))
    )
    (net (code "72") (name "Net-(K3-NO)") (class "Default")
      (node (ref "J4") (pin "3") (pinfunction "3_3") (pintype "passive"))
      (node (ref "K3") (pin "5") (pinfunction "NO_5") (pintype "passive"))
    )
    (net (code "73") (name "Net-(K4-C)") (class "Default")
      (node (ref "J5") (pin "2") (pinfunction "2_2") (pintype "passive"))
      (node (ref "K4") (pin "3") (pinfunction "C_3") (pintype "passive"))
    )
    (net (code "74") (name "Net-(K4-NC)") (class "Default")
      (node (ref "J5") (pin "1") (pinfunction "1_1") (pintype "passive"))
      (node (ref "K4") (pin "4") (pinfunction "NC_4") (pintype "passive"))
    )
    (net (code "75") (name "Net-(K4-NO)") (class "Default")
      (node (ref "J5") (pin "3") (pinfunction "3_3") (pintype "passive"))
      (node (ref "K4") (pin "5") (pinfunction "NO_5") (pintype "passive"))
    )
    (net (code "76") (name "Net-(K5-C)") (class "Default")
      (node (ref "J6") (pin "2") (pinfunction "2_2") (pintype "passive"))
      (node (ref "K5") (pin "3") (pinfunction "C_3") (pintype "passive"))
    )
    (net (code "77") (name "Net-(K5-NC)") (class "Default")
      (node (ref "J6") (pin "1") (pinfunction "1_1") (pintype "passive"))
      (node (ref "K5") (pin "4") (pinfunction "NC_4") (pintype "passive"))
    )
    (net (code "78") (name "Net-(K5-NO)") (class "Default")
      (node (ref "J6") (pin "3") (pinfunction "3_3") (pintype "passive"))
      (node (ref "K5") (pin "5") (pinfunction "NO_5") (pintype "passive"))
    )
    (net (code "79") (name "Net-(K6-C)") (class "Default")
      (node (ref "J7") (pin "2") (pinfunction "2_2") (pintype "passive"))
      (node (ref "K6") (pin "3") (pinfunction "C_3") (pintype "passive"))
    )
    (net (code "80") (name "Net-(K6-NC)") (class "Default")
      (node (ref "J7") (pin "1") (pinfunction "1_1") (pintype "passive"))
      (node (ref "K6") (pin "4") (pinfunction "NC_4") (pintype "passive"))
    )
    (net (code "81") (name "Net-(K6-NO)") (class "Default")
      (node (ref "J7") (pin "3") (pinfunction "3_3") (pintype "passive"))
      (node (ref "K6") (pin "5") (pinfunction "NO_5") (pintype "passive"))
    )
    (net (code "82") (name "Net-(K7-C)") (class "Default")
      (node (ref "J8") (pin "2") (pinfunction "2_2") (pintype "passive"))
      (node (ref "K7") (pin "3") (pinfunction "C_3") (pintype "passive"))
    )
    (net (code "83") (name "Net-(K7-NC)") (class "Default")
      (node (ref "J8") (pin "1") (pinfunction "1_1") (pintype "passive"))
      (node (ref "K7") (pin "4") (pinfunction "NC_4") (pintype "passive"))
    )
    (net (code "84") (name "Net-(K7-NO)") (class "Default")
      (node (ref "J8") (pin "3") (pinfunction "3_3") (pintype "passive"))
      (node (ref "K7") (pin "5") (pinfunction "NO_5") (pintype "passive"))
    )
    (net (code "85") (name "Net-(K8-C)") (class "Default")
      (node (ref "J9") (pin "2") (pinfunction "2_2") (pintype "passive"))
      (node (ref "K8") (pin "3") (pinfunction "C_3") (pintype "passive"))
    )
    (net (code "86") (name "Net-(K8-NC)") (class "Default")
      (node (ref "J9") (pin "1") (pinfunction "1_1") (pintype "passive"))
      (node (ref "K8") (pin "4") (pinfunction "NC_4") (pintype "passive"))
    )
    (net (code "87") (name "Net-(K8-NO)") (class "Default")
      (node (ref "J9") (pin "3") (pinfunction "3_3") (pintype "passive"))
      (node (ref "K8") (pin "5") (pinfunction "NO_5") (pintype "passive"))
    )
    (net (code "88") (name "Net-(LED1-Pad1)") (class "Default")
      (node (ref "LED1") (pin "1") (pinfunction "1_1") (pintype "passive"))
      (node (ref "R25") (pin "1") (pinfunction "1_1") (pintype "passive"))
    )
    (net (code "89") (name "Net-(LED2-Pad1)") (class "Default")
      (node (ref "LED2") (pin "1") (pinfunction "1_1") (pintype "passive"))
      (node (ref "R26") (pin "1") (pinfunction "1_1") (pintype "passive"))
    )
    (net (code "90") (name "Net-(LED3-Pad1)") (class "Default")
      (node (ref "LED3") (pin "1") (pinfunction "1_1") (pintype "passive"))
      (node (ref "R27") (pin "1") (pinfunction "1_1") (pintype "passive"))
    )
    (net (code "91") (name "Net-(LED4-Pad1)") (class "Default")
      (node (ref "LED4") (pin "1") (pinfunction "1_1") (pintype "passive"))
      (node (ref "R28") (pin "1") (pinfunction "1_1") (pintype "passive"))
    )
    (net (code "92") (name "Net-(LED5-Pad1)") (class "Default")
      (node (ref "LED5") (pin "1") (pinfunction "1_1") (pintype "passive"))
      (node (ref "R29") (pin "1") (pinfunction "1_1") (pintype "passive"))
    )
    (net (code "93") (name "Net-(LED6-Pad1)") (class "Default")
      (node (ref "LED6") (pin "1") (pinfunction "1_1") (pintype "passive"))
      (node (ref "R30") (pin "1") (pinfunction "1_1") (pintype "passive"))
    )
    (net (code "94") (name "Net-(LED7-Pad1)") (class "Default")
      (node (ref "LED7") (pin "1") (pinfunction "1_1") (pintype "passive"))
      (node (ref "R31") (pin "1") (pinfunction "1_1") (pintype "passive"))
    )
    (net (code "95") (name "Net-(LED8-Pad1)") (class "Default")
      (node (ref "LED8") (pin "1") (pinfunction "1_1") (pintype "passive"))
      (node (ref "R32") (pin "1") (pinfunction "1_1") (pintype "passive"))
    )
    (net (code "96") (name "Net-(Q1-G)") (class "Default")
      (node (ref "Q1") (pin "1") (pinfunction "G_1") (pintype "passive"))
      (node (ref "R3") (pin "2") (pinfunction "2_2") (pintype "passive"))
      (node (ref "R5") (pin "1") (pinfunction "1_1") (pintype "passive"))
    )
    (net (code "97") (name "Net-(Q2-G)") (class "Default")
      (node (ref "Q2") (pin "1") (pinfunction "G_1") (pintype "passive"))
      (node (ref "R4") (pin "2") (pinfunction "2_2") (pintype "passive"))
      (node (ref "R6") (pin "1") (pinfunction "1_1") (pintype "passive"))
    )
    (net (code "98") (name "Net-(Q3-G)") (class "Default")
      (node (ref "Q3") (pin "1") (pinfunction "G_1") (pintype "passive"))
      (node (ref "R11") (pin "1") (pinfunction "1_1") (pintype "passive"))
      (node (ref "R9") (pin "2") (pinfunction "2_2") (pintype "passive"))
    )
    (net (code "99") (name "Net-(Q4-G)") (class "Default")
      (node (ref "Q4") (pin "1") (pinfunction "G_1") (pintype "passive"))
      (node (ref "R10") (pin "2") (pinfunction "2_2") (pintype "passive"))
      (node (ref "R12") (pin "1") (pinfunction "1_1") (pintype "passive"))
    )
    (net (code "100") (name "Net-(Q5-G)") (class "Default")
      (node (ref "Q5") (pin "1") (pinfunction "G_1") (pintype "passive"))
      (node (ref "R15") (pin "2") (pinfunction "2_2") (pintype "passive"))
      (node (ref "R17") (pin "1") (pinfunction "1_1") (pintype "passive"))
    )
    (net (code "101") (name "Net-(Q6-G)") (class "Default")
      (node (ref "Q6") (pin "1") (pinfunction "G_1") (pintype "passive"))
      (node (ref "R16") (pin "2") (pinfunction "2_2") (pintype "passive"))
      (node (ref "R18") (pin "1") (pinfunction "1_1") (pintype "passive"))
    )
    (net (code "102") (name "Net-(Q7-G)") (class "Default")
      (node (ref "Q7") (pin "1") (pinfunction "G_1") (pintype "passive"))
      (node (ref "R21") (pin "2") (pinfunction "2_2") (pintype "passive"))
      (node (ref "R23") (pin "1") (pinfunction "1_1") (pintype "passive"))
    )
    (net (code "103") (name "Net-(Q8-G)") (class "Default")
      (node (ref "Q8") (pin "1") (pinfunction "G_1") (pintype "passive"))
      (node (ref "R22") (pin "2") (pinfunction "2_2") (pintype "passive"))
      (node (ref "R24") (pin "1") (pinfunction "1_1") (pintype "passive"))
    )
    (net (code "104") (name "unconnected-(BluePill1-C13-Pad2)") (class "Default")
      (node (ref "BluePill1") (pin "2") (pinfunction "C13_2") (pintype "power_in"))
    )
    (net (code "105") (name "unconnected-(BluePill1-C14-Pad3)") (class "Default")
      (node (ref "BluePill1") (pin "3") (pinfunction "C14_3") (pintype "power_in"))
    )
    (net (code "106") (name "unconnected-(BluePill1-C15-Pad4)") (class "Default")
      (node (ref "BluePill1") (pin "4") (pinfunction "C15_4") (pintype "power_in"))
    )
    (net (code "107") (name "unconnected-(J1-4-Pad2)") (class "Default")
      (node (ref "J1") (pin "2") (pinfunction "4_2") (pintype "passive"))
    )
  )
)
